# Weatstone_bridge.net
KiCad netlist of a schematic drawn in Altium Designer
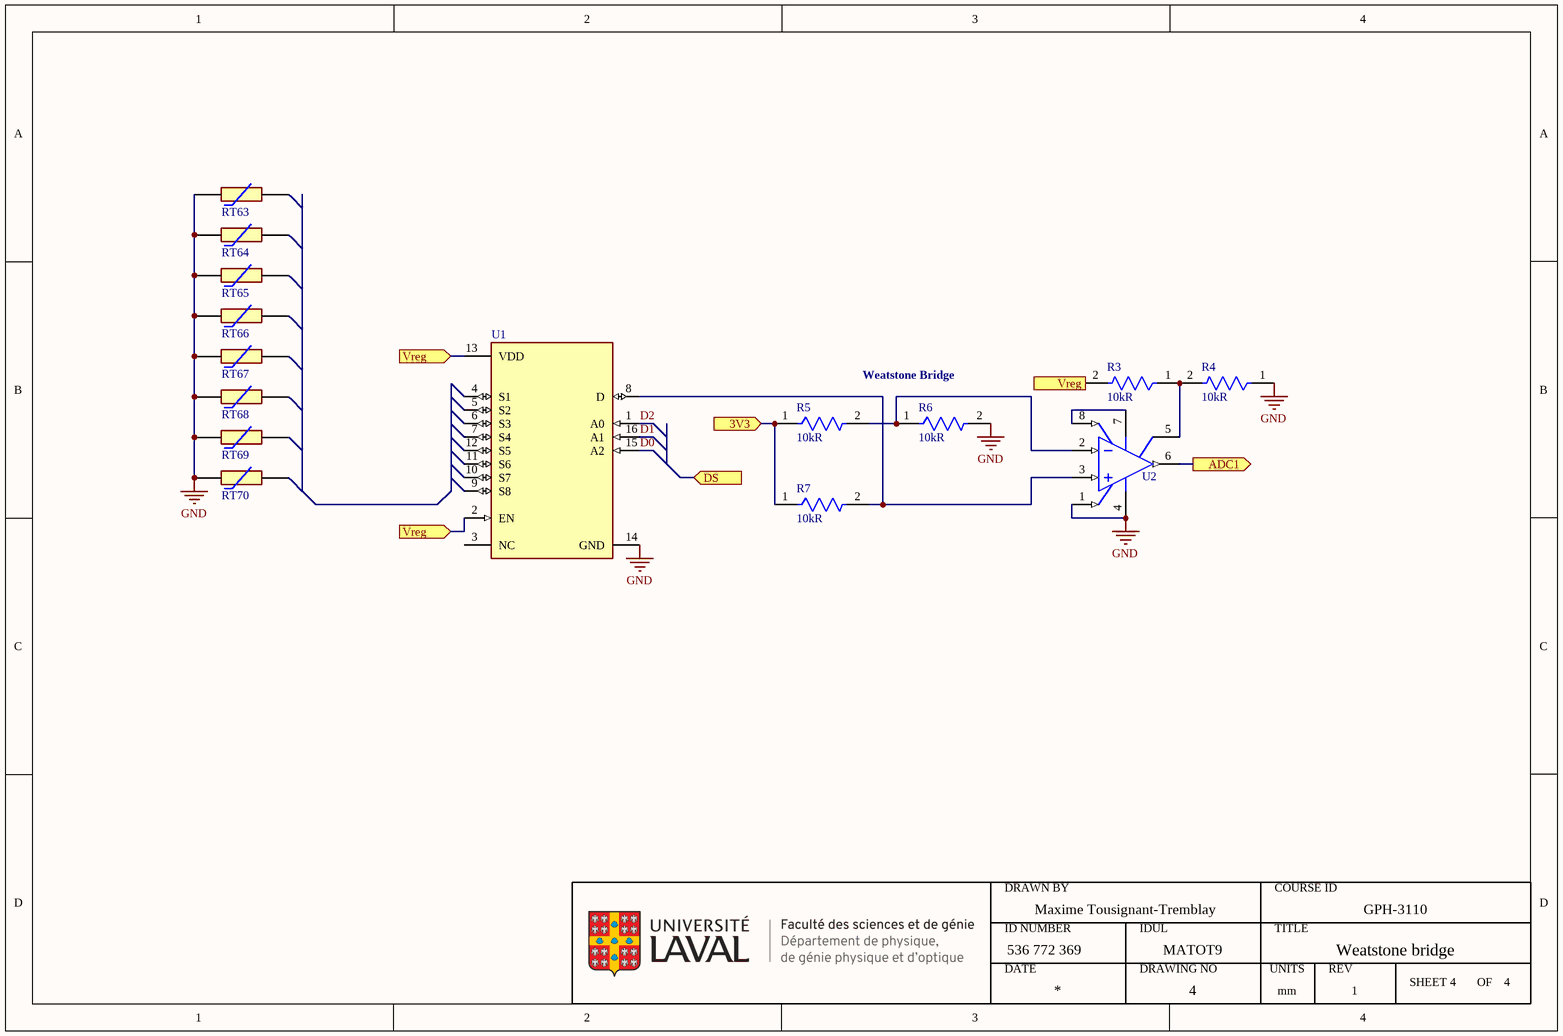
[diagram p0: Weatstone bridge.SchDoc]

(export (version "E")
  (design (tool "Eeschema 10.0.6"))
  (components
    (comp (ref "*3")
      (value "ULaval FSG-DPGPO")
      (libsource (lib "ULaval Title Block") (part "ULaval FSG-DPGPO"))
    )
    (comp (ref "R3")
      (value "10kR")
      (footprint "FP-RT0603-IPC_C")
      (description "Res High precision Thin Film 0603 10K Ohm 0.1% 1/10W ±25ppm/°C Molded SMD Paper T/R")
      (fields (field (name "Comment") "RT0603BRD0710KL"))
      (libsource (lib "Laval University") (part "1029c3af85768c4190bb7ad29bc67b5"))
    )
    (comp (ref "R4")
      (value "10kR")
      (footprint "FP-RT0603-IPC_C")
      (description "Res High precision Thin Film 0603 10K Ohm 0.1% 1/10W ±25ppm/°C Molded SMD Paper T/R")
      (fields (field (name "Comment") "RT0603BRD0710KL"))
      (libsource (lib "Laval University") (part "1029c3af85768c4190bb7ad29bc67b5"))
    )
    (comp (ref "R5")
      (value "10kR")
      (footprint "FP-RT0603-IPC_C")
      (description "Res High precision Thin Film 0603 10K Ohm 0.1% 1/10W ±25ppm/°C Molded SMD Paper T/R")
      (fields (field (name "Comment") "RT0603BRD0710KL"))
      (libsource (lib "Laval University") (part "1029c3af85768c4190bb7ad29bc67b5"))
    )
    (comp (ref "R6")
      (value "10kR")
      (footprint "FP-RT0603-IPC_C")
      (description "Res High precision Thin Film 0603 10K Ohm 0.1% 1/10W ±25ppm/°C Molded SMD Paper T/R")
      (fields (field (name "Comment") "RT0603BRD0710KL"))
      (libsource (lib "Laval University") (part "1029c3af85768c4190bb7ad29bc67b5"))
    )
    (comp (ref "R7")
      (value "10kR")
      (footprint "FP-RT0603-IPC_C")
      (description "Res High precision Thin Film 0603 10K Ohm 0.1% 1/10W ±25ppm/°C Molded SMD Paper T/R")
      (fields (field (name "Comment") "RT0603BRD0710KL"))
      (libsource (lib "Laval University") (part "1029c3af85768c4190bb7ad29bc67b5"))
    )
    (comp (ref "RT63")
      (value "NTCLE350E4103FHB0")
      (footprint "SamacSys:NTCLE350E4103FHB0")
      (description "Thermistor")
      (libsource (lib "*") (part "NTCLE350E4103FHB0"))
    )
    (comp (ref "RT64")
      (value "NTCLE350E4103FHB0")
      (footprint "SamacSys:NTCLE350E4103FHB0")
      (description "Thermistor")
      (libsource (lib "*") (part "NTCLE350E4103FHB0"))
    )
    (comp (ref "RT65")
      (value "NTCLE350E4103FHB0")
      (footprint "SamacSys:NTCLE350E4103FHB0")
      (description "Thermistor")
      (libsource (lib "*") (part "NTCLE350E4103FHB0"))
    )
    (comp (ref "RT66")
      (value "NTCLE350E4103FHB0")
      (footprint "SamacSys:NTCLE350E4103FHB0")
      (description "Thermistor")
      (libsource (lib "*") (part "NTCLE350E4103FHB0"))
    )
    (comp (ref "RT67")
      (value "NTCLE350E4103FHB0")
      (footprint "SamacSys:NTCLE350E4103FHB0")
      (description "Thermistor")
      (libsource (lib "*") (part "NTCLE350E4103FHB0"))
    )
    (comp (ref "RT68")
      (value "NTCLE350E4103FHB0")
      (footprint "SamacSys:NTCLE350E4103FHB0")
      (description "Thermistor")
      (libsource (lib "*") (part "NTCLE350E4103FHB0"))
    )
    (comp (ref "RT69")
      (value "NTCLE350E4103FHB0")
      (footprint "SamacSys:NTCLE350E4103FHB0")
      (description "Thermistor")
      (libsource (lib "*") (part "NTCLE350E4103FHB0"))
    )
    (comp (ref "RT70")
      (value "NTCLE350E4103FHB0")
      (footprint "SamacSys:NTCLE350E4103FHB0")
      (description "Thermistor")
      (libsource (lib "*") (part "NTCLE350E4103FHB0"))
    )
    (comp (ref "U1")
      (value "TMUX1208PWR")
      (footprint "FP-PW0016A-IPC_B")
      (description "5-V, 8: 1, 1-channel general-purpose analog multiplexer with 1.8-V input logic 16-TSSOP -40 to 125")
      (libsource (lib "Laval University") (part "3fc1eebd4caa5623a46538ca285a60d"))
    )
    (comp (ref "U2")
      (value "MCP6N11-100E/SN")
      (footprint "SOIC-SN8_L")
      (description "MCP6N11 Series Single Channel 500 KHz 5.5 V Instrumentation Amplifier - SOIC-8")
      (libsource (lib "Laval University") (part "AMP-INA-MCP6N11-IL8"))
    )
  )
  (nets
    (net (code "1") (name "/3V3") (class "Default")
      (node (ref "R5") (pin "1") (pinfunction "1_1") (pintype "passive"))
      (node (ref "R7") (pin "1") (pinfunction "1_1") (pintype "passive"))
    )
    (net (code "2") (name "/ADC1") (class "Default")
      (node (ref "U2") (pin "6") (pinfunction "VOUT_6") (pintype "output"))
    )
    (net (code "3") (name "/D0") (class "Default")
      (node (ref "U1") (pin "15") (pinfunction "A2_15") (pintype "input"))
    )
    (net (code "4") (name "/D1") (class "Default")
      (node (ref "U1") (pin "16") (pinfunction "A1_16") (pintype "input"))
    )
    (net (code "5") (name "/D2") (class "Default")
      (node (ref "U1") (pin "1") (pinfunction "A0_1") (pintype "input"))
    )
    (net (code "7") (name "/Vreg") (class "Default")
      (node (ref "R3") (pin "2") (pinfunction "2_2") (pintype "passive"))
      (node (ref "U1") (pin "13") (pinfunction "VDD_13") (pintype "power_in"))
      (node (ref "U1") (pin "2") (pinfunction "EN_2") (pintype "input"))
    )
    (net (code "8") (name "GND") (class "Default")
      (node (ref "R4") (pin "1") (pinfunction "1_1") (pintype "passive"))
      (node (ref "R6") (pin "2") (pinfunction "2_2") (pintype "passive"))
      (node (ref "RT63") (pin "1") (pinfunction "1_1") (pintype "passive"))
      (node (ref "RT64") (pin "1") (pinfunction "1_1") (pintype "passive"))
      (node (ref "RT65") (pin "1") (pinfunction "1_1") (pintype "passive"))
      (node (ref "RT66") (pin "1") (pinfunction "1_1") (pintype "passive"))
      (node (ref "RT67") (pin "1") (pinfunction "1_1") (pintype "passive"))
      (node (ref "RT68") (pin "1") (pinfunction "1_1") (pintype "passive"))
      (node (ref "RT69") (pin "1") (pinfunction "1_1") (pintype "passive"))
      (node (ref "RT70") (pin "1") (pinfunction "1_1") (pintype "passive"))
      (node (ref "U1") (pin "14") (pinfunction "GND_14") (pintype "power_in"))
      (node (ref "U2") (pin "1") (pinfunction "VFG_1") (pintype "input"))
      (node (ref "U2") (pin "4") (pinfunction "VSS_4") (pintype "power_in"))
    )
    (net (code "9") (name "Net-(U1-D)") (class "Default")
      (node (ref "R7") (pin "2") (pinfunction "2_2") (pintype "passive"))
      (node (ref "U1") (pin "8") (pinfunction "D_8") (pintype "bidirectional"))
      (node (ref "U2") (pin "3") (pinfunction "VIP_3") (pintype "input"))
    )
    (net (code "10") (name "Net-(U2-EN{slash}~{CAL})") (class "Default")
      (node (ref "U2") (pin "7") (pinfunction "VDD_7") (pintype "power_in"))
      (node (ref "U2") (pin "8") (pinfunction "EN/~{CAL}_8") (pintype "input"))
    )
    (net (code "11") (name "Net-(U2-VIM)") (class "Default")
      (node (ref "R5") (pin "2") (pinfunction "2_2") (pintype "passive"))
      (node (ref "R6") (pin "1") (pinfunction "1_1") (pintype "passive"))
      (node (ref "U2") (pin "2") (pinfunction "VIM_2") (pintype "input"))
    )
    (net (code "12") (name "Net-(U2-VREF)") (class "Default")
      (node (ref "R3") (pin "1") (pinfunction "1_1") (pintype "passive"))
      (node (ref "R4") (pin "2") (pinfunction "2_2") (pintype "passive"))
      (node (ref "U2") (pin "5") (pinfunction "VREF_5") (pintype "power_in"))
    )
    (net (code "13") (name "unconnected-(RT63-Pad2)") (class "Default")
      (node (ref "RT63") (pin "2") (pinfunction "2_2") (pintype "passive"))
    )
    (net (code "14") (name "unconnected-(RT64-Pad2)") (class "Default")
      (node (ref "RT64") (pin "2") (pinfunction "2_2") (pintype "passive"))
    )
    (net (code "15") (name "unconnected-(RT65-Pad2)") (class "Default")
      (node (ref "RT65") (pin "2") (pinfunction "2_2") (pintype "passive"))
    )
    (net (code "16") (name "unconnected-(RT66-Pad2)") (class "Default")
      (node (ref "RT66") (pin "2") (pinfunction "2_2") (pintype "passive"))
    )
    (net (code "17") (name "unconnected-(RT67-Pad2)") (class "Default")
      (node (ref "RT67") (pin "2") (pinfunction "2_2") (pintype "passive"))
    )
    (net (code "18") (name "unconnected-(RT68-Pad2)") (class "Default")
      (node (ref "RT68") (pin "2") (pinfunction "2_2") (pintype "passive"))
    )
    (net (code "19") (name "unconnected-(RT69-Pad2)") (class "Default")
      (node (ref "RT69") (pin "2") (pinfunction "2_2") (pintype "passive"))
    )
    (net (code "20") (name "unconnected-(RT70-Pad2)") (class "Default")
      (node (ref "RT70") (pin "2") (pinfunction "2_2") (pintype "passive"))
    )
    (net (code "21") (name "unconnected-(U1-NC-Pad3)") (class "Default")
      (node (ref "U1") (pin "3") (pinfunction "NC_3") (pintype "passive"))
    )
    (net (code "22") (name "unconnected-(U1-S1-Pad4)") (class "Default")
      (node (ref "U1") (pin "4") (pinfunction "S1_4") (pintype "bidirectional"))
    )
    (net (code "23") (name "unconnected-(U1-S2-Pad5)") (class "Default")
      (node (ref "U1") (pin "5") (pinfunction "S2_5") (pintype "bidirectional"))
    )
    (net (code "24") (name "unconnected-(U1-S3-Pad6)") (class "Default")
      (node (ref "U1") (pin "6") (pinfunction "S3_6") (pintype "bidirectional"))
    )
    (net (code "25") (name "unconnected-(U1-S4-Pad7)") (class "Default")
      (node (ref "U1") (pin "7") (pinfunction "S4_7") (pintype "bidirectional"))
    )
    (net (code "26") (name "unconnected-(U1-S5-Pad12)") (class "Default")
      (node (ref "U1") (pin "12") (pinfunction "S5_12") (pintype "bidirectional"))
    )
    (net (code "27") (name "unconnected-(U1-S6-Pad11)") (class "Default")
      (node (ref "U1") (pin "11") (pinfunction "S6_11") (pintype "bidirectional"))
    )
    (net (code "28") (name "unconnected-(U1-S7-Pad10)") (class "Default")
      (node (ref "U1") (pin "10") (pinfunction "S7_10") (pintype "bidirectional"))
    )
    (net (code "29") (name "unconnected-(U1-S8-Pad9)") (class "Default")
      (node (ref "U1") (pin "9") (pinfunction "S8_9") (pintype "bidirectional"))
    )
  )
)
